# power.net
KiCad netlist of a schematic drawn in EAGLE
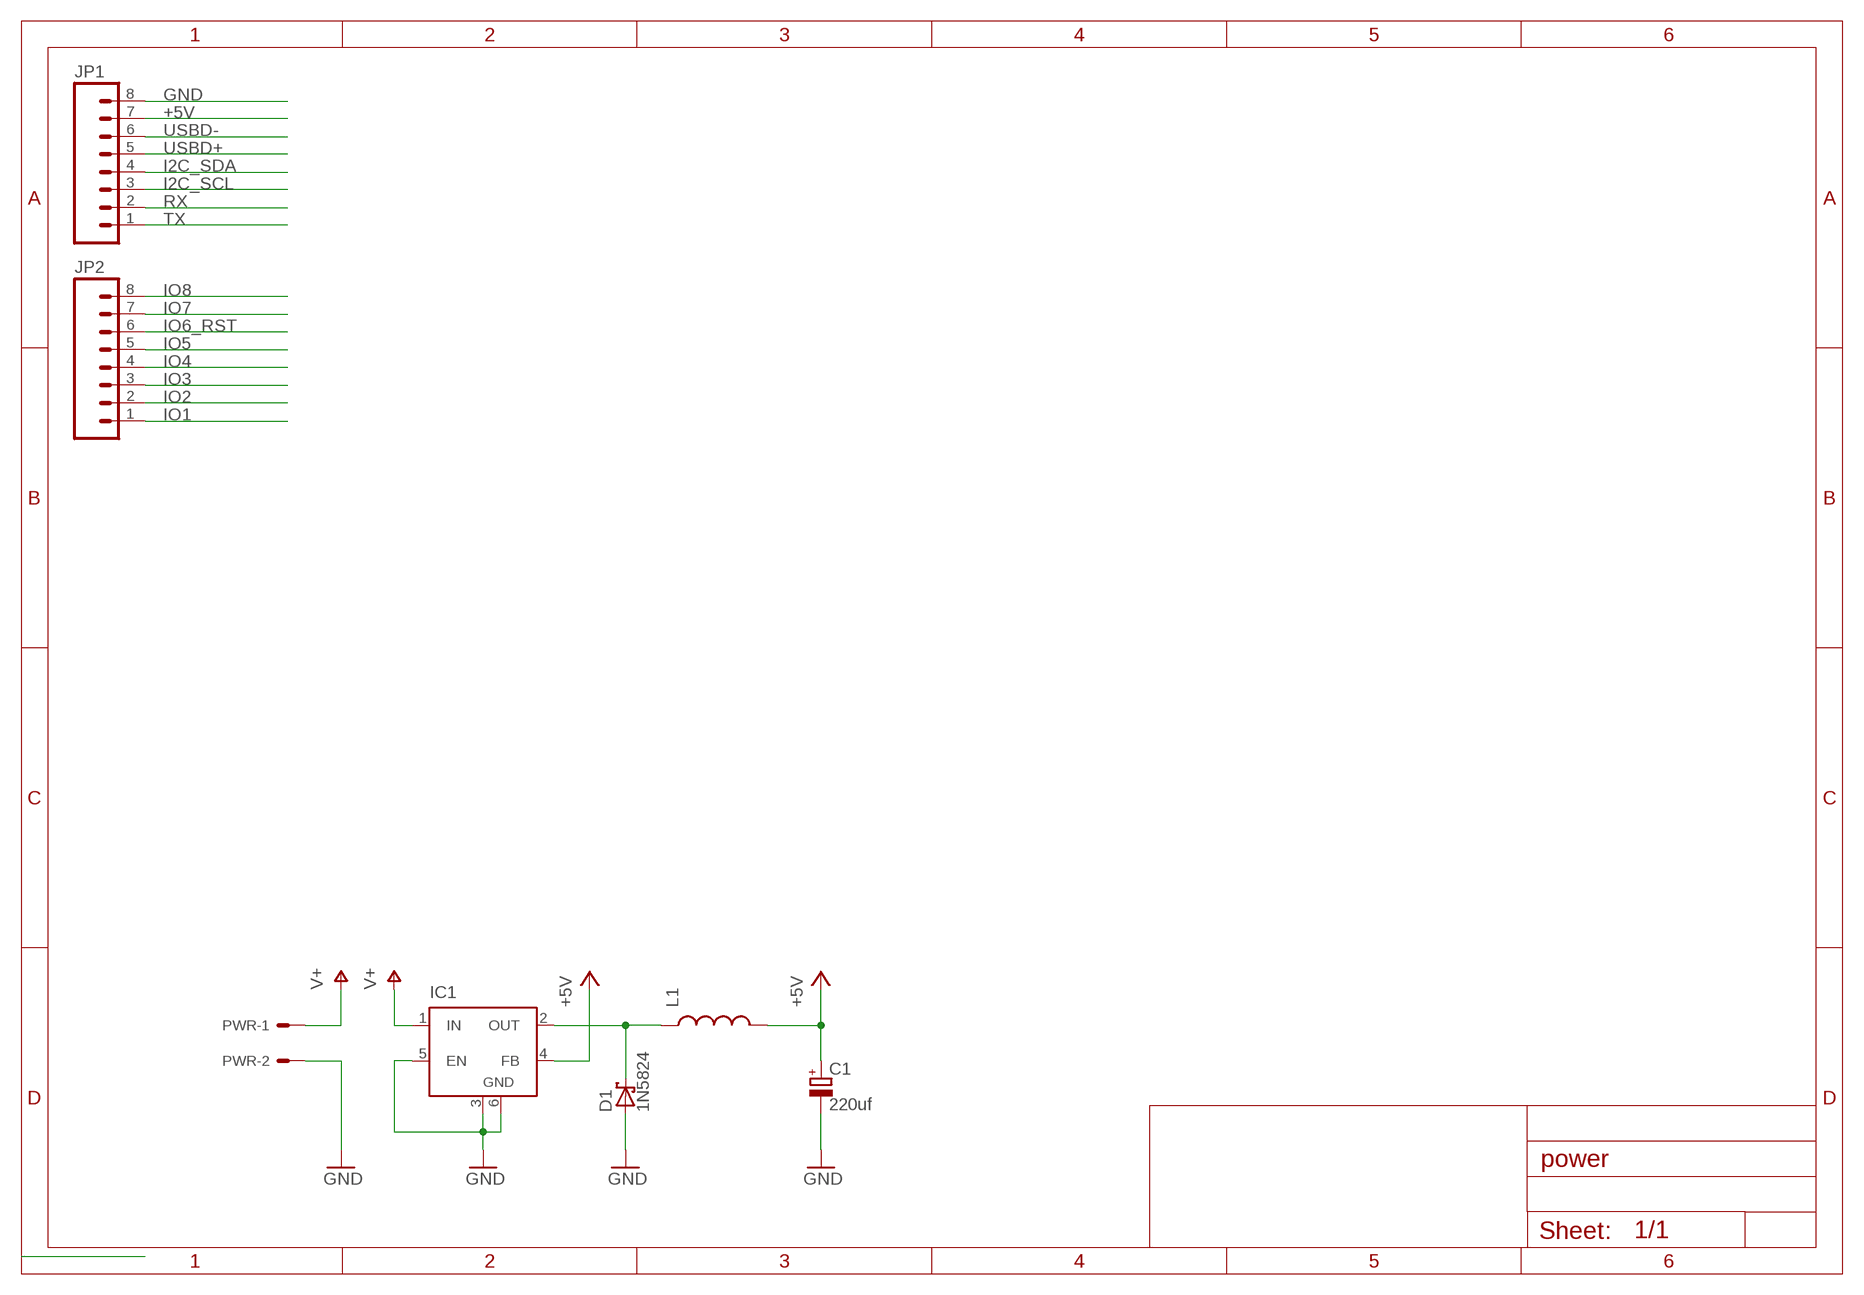
[diagram p0: schematic, sheet 1]

(export (version "E")
  (design (tool "Eeschema 10.0.6"))
  (components
    (comp (ref "C1")
      (value "220uf")
      (footprint "eagle-import:E2,5-6")
      (libsource (lib "eagle-import") (part "CPOL-EUE2.5-6"))
    )
    (comp (ref "D1")
      (value "1N5824")
      (footprint "eagle-import:DO41-7.6")
      (libsource (lib "eagle-import") (part "1N5817-B"))
    )
    (comp (ref "IC1")
      (value "LM2596S")
      (footprint "eagle-import:TO263-5")
      (libsource (lib "eagle-import") (part "LM2596S"))
    )
    (comp (ref "JP1")
      (value "M081X08")
      (footprint "eagle-import:1X08")
      (libsource (lib "eagle-import") (part "M081X08"))
    )
    (comp (ref "JP2")
      (value "M081X08")
      (footprint "eagle-import:1X08")
      (libsource (lib "eagle-import") (part "M081X08"))
    )
    (comp (ref "L1")
      (value "INDUCTORSRU1038")
      (footprint "eagle-import:SRU1038")
      (libsource (lib "eagle-import") (part "INDUCTORSRU1038"))
    )
    (comp (ref "PWR")
      (value "22-05-7028-02")
      (footprint "eagle-import:7395-02")
      (libsource (lib "eagle-import") (part "22-?-0205-7028"))
    )
  )
  (nets
    (net (code "1") (name "+5V") (class "Default")
      (node (ref "C1") (pin "+") (pinfunction "+_+") (pintype "passive"))
      (node (ref "IC1") (pin "4") (pinfunction "FB_4") (pintype "input"))
      (node (ref "JP1") (pin "7") (pinfunction "7_7") (pintype "passive"))
      (node (ref "L1") (pin "2") (pinfunction "2_2") (pintype "passive"))
    )
    (net (code "2") (name "/I2C_SCL") (class "Default")
      (node (ref "JP1") (pin "3") (pinfunction "3_3") (pintype "passive"))
    )
    (net (code "3") (name "/I2C_SDA") (class "Default")
      (node (ref "JP1") (pin "4") (pinfunction "4_4") (pintype "passive"))
    )
    (net (code "4") (name "/IO1") (class "Default")
      (node (ref "JP2") (pin "1") (pinfunction "1_1") (pintype "passive"))
    )
    (net (code "5") (name "/IO2") (class "Default")
      (node (ref "JP2") (pin "2") (pinfunction "2_2") (pintype "passive"))
    )
    (net (code "6") (name "/IO3") (class "Default")
      (node (ref "JP2") (pin "3") (pinfunction "3_3") (pintype "passive"))
    )
    (net (code "7") (name "/IO4") (class "Default")
      (node (ref "JP2") (pin "4") (pinfunction "4_4") (pintype "passive"))
    )
    (net (code "8") (name "/IO5") (class "Default")
      (node (ref "JP2") (pin "5") (pinfunction "5_5") (pintype "passive"))
    )
    (net (code "9") (name "/IO6_RST") (class "Default")
      (node (ref "JP2") (pin "6") (pinfunction "6_6") (pintype "passive"))
    )
    (net (code "10") (name "/IO7") (class "Default")
      (node (ref "JP2") (pin "7") (pinfunction "7_7") (pintype "passive"))
    )
    (net (code "11") (name "/IO8") (class "Default")
      (node (ref "JP2") (pin "8") (pinfunction "8_8") (pintype "passive"))
    )
    (net (code "12") (name "/RX") (class "Default")
      (node (ref "JP1") (pin "2") (pinfunction "2_2") (pintype "passive"))
    )
    (net (code "13") (name "/TX") (class "Default")
      (node (ref "JP1") (pin "1") (pinfunction "1_1") (pintype "passive"))
    )
    (net (code "14") (name "/USBD+") (class "Default")
      (node (ref "JP1") (pin "5") (pinfunction "5_5") (pintype "passive"))
    )
    (net (code "15") (name "/USBD-") (class "Default")
      (node (ref "JP1") (pin "6") (pinfunction "6_6") (pintype "passive"))
    )
    (net (code "16") (name "GND") (class "Default")
      (node (ref "C1") (pin "-") (pinfunction "-_-") (pintype "passive"))
      (node (ref "D1") (pin "A") (pinfunction "A_A") (pintype "passive"))
      (node (ref "IC1") (pin "3") (pinfunction "GND_3") (pintype "power_in"))
      (node (ref "IC1") (pin "5") (pinfunction "EN_5") (pintype "input"))
      (node (ref "IC1") (pin "6") (pinfunction "GND_6") (pintype "power_in"))
      (node (ref "JP1") (pin "8") (pinfunction "8_8") (pintype "passive"))
      (node (ref "PWR") (pin "2") (pinfunction "S_2") (pintype "passive"))
    )
    (net (code "17") (name "Net-(IC1-OUT)") (class "Default")
      (node (ref "D1") (pin "C") (pinfunction "C_C") (pintype "passive"))
      (node (ref "IC1") (pin "2") (pinfunction "OUT_2") (pintype "output"))
      (node (ref "L1") (pin "1") (pinfunction "1_1") (pintype "passive"))
    )
    (net (code "18") (name "V+") (class "Default")
      (node (ref "IC1") (pin "1") (pinfunction "IN_1") (pintype "input"))
      (node (ref "PWR") (pin "1") (pinfunction "S_1") (pintype "passive"))
    )
  )
)
